# SupportMachineTest.net
KiCad netlist of a schematic drawn in EAGLE
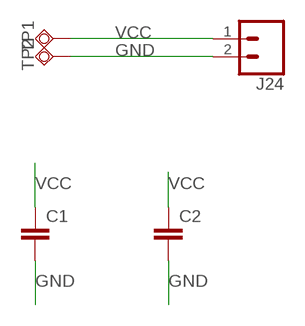
[diagram p0: schematic, sheet 1]

(export (version "E")
  (design (tool "Eeschema 10.0.6"))
  (components
    (comp (ref "C1")
      (value "CAP-1206")
      (footprint "eagle-import:1206")
      (libsource (lib "eagle-import") (part "CAP-1206"))
    )
    (comp (ref "C2")
      (value "CAP0805")
      (footprint "eagle-import:0805")
      (libsource (lib "eagle-import") (part "CAP0805"))
    )
    (comp (ref "J24")
      (value "CONN_02")
      (footprint "eagle-import:1X02")
      (libsource (lib "eagle-import") (part "CONN_02"))
    )
    (comp (ref "TP1")
      (value "TESTPAD_TPSQTP20SQ")
      (footprint "eagle-import:TESTPAD_TP20SQ")
      (libsource (lib "eagle-import") (part "TESTPAD_TPSQTP20SQ"))
    )
    (comp (ref "TP2")
      (value "TESTPAD_TPSQTP20SQ")
      (footprint "eagle-import:TESTPAD_TP20SQ")
      (libsource (lib "eagle-import") (part "TESTPAD_TPSQTP20SQ"))
    )
  )
  (nets
    (net (code "1") (name "/GND") (class "Default")
      (node (ref "C1") (pin "2") (pinfunction "2_2") (pintype "passive"))
      (node (ref "C2") (pin "2") (pinfunction "2_2") (pintype "passive"))
      (node (ref "J24") (pin "2") (pinfunction "2_2") (pintype "passive"))
      (node (ref "TP2") (pin "TP") (pinfunction "TP_TP") (pintype "input"))
    )
    (net (code "2") (name "/VCC") (class "Default")
      (node (ref "C1") (pin "1") (pinfunction "1_1") (pintype "passive"))
      (node (ref "C2") (pin "1") (pinfunction "1_1") (pintype "passive"))
      (node (ref "J24") (pin "1") (pinfunction "1_1") (pintype "passive"))
      (node (ref "TP1") (pin "TP") (pinfunction "TP_TP") (pintype "input"))
    )
  )
)
